# schemprzes.net
KiCad netlist of a schematic drawn in EAGLE
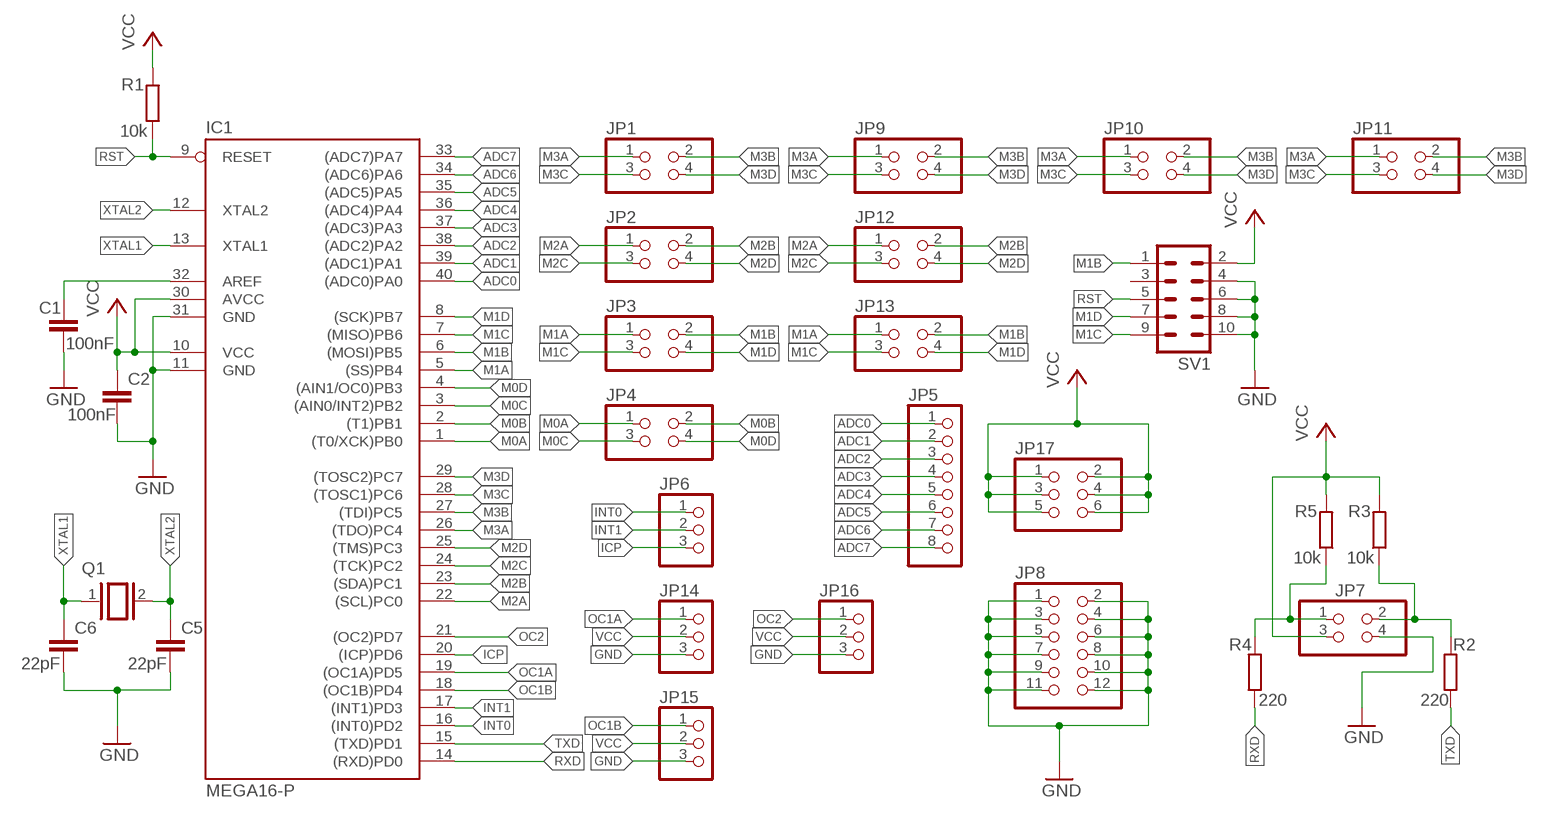
[diagram p0: schematic, sheet 1]

(export (version "E")
  (design (tool "Eeschema 10.0.6"))
  (components
    (comp (ref "C1")
      (value "100nF")
      (footprint "eagle-import:C0805")
      (libsource (lib "eagle-import") (part "C-EUC0805"))
    )
    (comp (ref "C2")
      (value "100nF")
      (footprint "eagle-import:C0805")
      (libsource (lib "eagle-import") (part "C-EUC0805"))
    )
    (comp (ref "C5")
      (value "22pF")
      (footprint "eagle-import:C0805")
      (libsource (lib "eagle-import") (part "C-EUC0805"))
    )
    (comp (ref "C6")
      (value "22pF")
      (footprint "eagle-import:C0805")
      (libsource (lib "eagle-import") (part "C-EUC0805"))
    )
    (comp (ref "IC1")
      (value "MEGA16-P")
      (footprint "eagle-import:DIL40")
      (fields (field (name "MPN") "ATMEGA16-16PU"))
      (libsource (lib "eagle-import") (part "MEGA16-P"))
    )
    (comp (ref "JP1")
      (value "PINHD-2X2")
      (footprint "eagle-import:2X02")
      (libsource (lib "eagle-import") (part "PINHD-2X2"))
    )
    (comp (ref "JP2")
      (value "PINHD-2X2")
      (footprint "eagle-import:2X02")
      (libsource (lib "eagle-import") (part "PINHD-2X2"))
    )
    (comp (ref "JP3")
      (value "PINHD-2X2")
      (footprint "eagle-import:2X02")
      (libsource (lib "eagle-import") (part "PINHD-2X2"))
    )
    (comp (ref "JP4")
      (value "PINHD-2X2")
      (footprint "eagle-import:2X02")
      (libsource (lib "eagle-import") (part "PINHD-2X2"))
    )
    (comp (ref "JP5")
      (value "PINHD-1X8")
      (footprint "eagle-import:1X08")
      (libsource (lib "eagle-import") (part "PINHD-1X8"))
    )
    (comp (ref "JP6")
      (value "PINHD-1X3")
      (footprint "eagle-import:1X03")
      (libsource (lib "eagle-import") (part "PINHD-1X3"))
    )
    (comp (ref "JP7")
      (value "PINHD-2X2")
      (footprint "eagle-import:2X02")
      (libsource (lib "eagle-import") (part "PINHD-2X2"))
    )
    (comp (ref "JP8")
      (value "PINHD-2X6")
      (footprint "eagle-import:2X06")
      (libsource (lib "eagle-import") (part "PINHD-2X6"))
    )
    (comp (ref "JP9")
      (value "PINHD-2X2")
      (footprint "eagle-import:2X02")
      (libsource (lib "eagle-import") (part "PINHD-2X2"))
    )
    (comp (ref "JP10")
      (value "PINHD-2X2")
      (footprint "eagle-import:2X02")
      (libsource (lib "eagle-import") (part "PINHD-2X2"))
    )
    (comp (ref "JP11")
      (value "PINHD-2X2")
      (footprint "eagle-import:2X02")
      (libsource (lib "eagle-import") (part "PINHD-2X2"))
    )
    (comp (ref "JP12")
      (value "PINHD-2X2")
      (footprint "eagle-import:2X02")
      (libsource (lib "eagle-import") (part "PINHD-2X2"))
    )
    (comp (ref "JP13")
      (value "PINHD-2X2")
      (footprint "eagle-import:2X02")
      (libsource (lib "eagle-import") (part "PINHD-2X2"))
    )
    (comp (ref "JP14")
      (value "PINHD-1X3")
      (footprint "eagle-import:1X03")
      (libsource (lib "eagle-import") (part "PINHD-1X3"))
    )
    (comp (ref "JP15")
      (value "PINHD-1X3")
      (footprint "eagle-import:1X03")
      (libsource (lib "eagle-import") (part "PINHD-1X3"))
    )
    (comp (ref "JP16")
      (value "PINHD-1X3")
      (footprint "eagle-import:1X03")
      (libsource (lib "eagle-import") (part "PINHD-1X3"))
    )
    (comp (ref "JP17")
      (value "PINHD-2X3")
      (footprint "eagle-import:2X03")
      (libsource (lib "eagle-import") (part "PINHD-2X3"))
    )
    (comp (ref "Q1")
      (value "XTAL/S")
      (footprint "eagle-import:QS")
      (libsource (lib "eagle-import") (part "XTAL/S"))
    )
    (comp (ref "R1")
      (value "10k")
      (footprint "eagle-import:R0805")
      (libsource (lib "eagle-import") (part "R-EU_R0805"))
    )
    (comp (ref "R2")
      (value "220")
      (footprint "eagle-import:R0805")
      (libsource (lib "eagle-import") (part "R-EU_R0805"))
    )
    (comp (ref "R3")
      (value "10k")
      (footprint "eagle-import:R0805")
      (libsource (lib "eagle-import") (part "R-EU_R0805"))
    )
    (comp (ref "R4")
      (value "220")
      (footprint "eagle-import:R0805")
      (libsource (lib "eagle-import") (part "R-EU_R0805"))
    )
    (comp (ref "R5")
      (value "10k")
      (footprint "eagle-import:R0805")
      (libsource (lib "eagle-import") (part "R-EU_R0805"))
    )
    (comp (ref "SV1")
      (value "ML10")
      (footprint "eagle-import:ML10")
      (libsource (lib "eagle-import") (part "ML10"))
    )
  )
  (nets
    (net (code "1") (name "ADC0") (class "Default")
      (node (ref "IC1") (pin "40") (pinfunction "(ADC0)PA0_40") (pintype "bidirectional"))
      (node (ref "JP5") (pin "1") (pinfunction "1_1") (pintype "passive"))
    )
    (net (code "2") (name "ADC1") (class "Default")
      (node (ref "IC1") (pin "39") (pinfunction "(ADC1)PA1_39") (pintype "bidirectional"))
      (node (ref "JP5") (pin "2") (pinfunction "2_2") (pintype "passive"))
    )
    (net (code "3") (name "ADC2") (class "Default")
      (node (ref "IC1") (pin "38") (pinfunction "(ADC2)PA2_38") (pintype "bidirectional"))
      (node (ref "JP5") (pin "3") (pinfunction "3_3") (pintype "passive"))
    )
    (net (code "4") (name "ADC3") (class "Default")
      (node (ref "IC1") (pin "37") (pinfunction "(ADC3)PA3_37") (pintype "bidirectional"))
      (node (ref "JP5") (pin "4") (pinfunction "4_4") (pintype "passive"))
    )
    (net (code "5") (name "ADC4") (class "Default")
      (node (ref "IC1") (pin "36") (pinfunction "(ADC4)PA4_36") (pintype "bidirectional"))
      (node (ref "JP5") (pin "5") (pinfunction "5_5") (pintype "passive"))
    )
    (net (code "6") (name "ADC5") (class "Default")
      (node (ref "IC1") (pin "35") (pinfunction "(ADC5)PA5_35") (pintype "bidirectional"))
      (node (ref "JP5") (pin "6") (pinfunction "6_6") (pintype "passive"))
    )
    (net (code "7") (name "ADC6") (class "Default")
      (node (ref "IC1") (pin "34") (pinfunction "(ADC6)PA6_34") (pintype "bidirectional"))
      (node (ref "JP5") (pin "7") (pinfunction "7_7") (pintype "passive"))
    )
    (net (code "8") (name "ADC7") (class "Default")
      (node (ref "IC1") (pin "33") (pinfunction "(ADC7)PA7_33") (pintype "bidirectional"))
      (node (ref "JP5") (pin "8") (pinfunction "8_8") (pintype "passive"))
    )
    (net (code "9") (name "GND") (class "Default")
      (node (ref "C1") (pin "2") (pinfunction "2_2") (pintype "passive"))
      (node (ref "C2") (pin "2") (pinfunction "2_2") (pintype "passive"))
      (node (ref "C5") (pin "2") (pinfunction "2_2") (pintype "passive"))
      (node (ref "C6") (pin "2") (pinfunction "2_2") (pintype "passive"))
      (node (ref "IC1") (pin "11") (pinfunction "GND_11") (pintype "power_in"))
      (node (ref "IC1") (pin "31") (pinfunction "GND_31") (pintype "power_in"))
      (node (ref "JP14") (pin "3") (pinfunction "3_3") (pintype "passive"))
      (node (ref "JP15") (pin "3") (pinfunction "3_3") (pintype "passive"))
      (node (ref "JP16") (pin "3") (pinfunction "3_3") (pintype "passive"))
      (node (ref "JP7") (pin "4") (pinfunction "4_4") (pintype "passive"))
      (node (ref "JP8") (pin "1") (pinfunction "1_1") (pintype "passive"))
      (node (ref "JP8") (pin "10") (pinfunction "10_10") (pintype "passive"))
      (node (ref "JP8") (pin "11") (pinfunction "11_11") (pintype "passive"))
      (node (ref "JP8") (pin "12") (pinfunction "12_12") (pintype "passive"))
      (node (ref "JP8") (pin "2") (pinfunction "2_2") (pintype "passive"))
      (node (ref "JP8") (pin "3") (pinfunction "3_3") (pintype "passive"))
      (node (ref "JP8") (pin "4") (pinfunction "4_4") (pintype "passive"))
      (node (ref "JP8") (pin "5") (pinfunction "5_5") (pintype "passive"))
      (node (ref "JP8") (pin "6") (pinfunction "6_6") (pintype "passive"))
      (node (ref "JP8") (pin "7") (pinfunction "7_7") (pintype "passive"))
      (node (ref "JP8") (pin "8") (pinfunction "8_8") (pintype "passive"))
      (node (ref "JP8") (pin "9") (pinfunction "9_9") (pintype "passive"))
      (node (ref "SV1") (pin "10") (pinfunction "10_10") (pintype "passive"))
      (node (ref "SV1") (pin "4") (pinfunction "4_4") (pintype "passive"))
      (node (ref "SV1") (pin "6") (pinfunction "6_6") (pintype "passive"))
      (node (ref "SV1") (pin "8") (pinfunction "8_8") (pintype "passive"))
    )
    (net (code "10") (name "ICP") (class "Default")
      (node (ref "IC1") (pin "20") (pinfunction "(ICP)PD6_20") (pintype "bidirectional"))
      (node (ref "JP6") (pin "3") (pinfunction "3_3") (pintype "passive"))
    )
    (net (code "11") (name "INT0") (class "Default")
      (node (ref "IC1") (pin "16") (pinfunction "(INT0)PD2_16") (pintype "bidirectional"))
      (node (ref "JP6") (pin "1") (pinfunction "1_1") (pintype "passive"))
    )
    (net (code "12") (name "INT1") (class "Default")
      (node (ref "IC1") (pin "17") (pinfunction "(INT1)PD3_17") (pintype "bidirectional"))
      (node (ref "JP6") (pin "2") (pinfunction "2_2") (pintype "passive"))
    )
    (net (code "13") (name "M0A") (class "Default")
      (node (ref "IC1") (pin "1") (pinfunction "(T0/XCK)PB0_1") (pintype "bidirectional"))
      (node (ref "JP4") (pin "1") (pinfunction "1_1") (pintype "passive"))
    )
    (net (code "14") (name "M0B") (class "Default")
      (node (ref "IC1") (pin "2") (pinfunction "(T1)PB1_2") (pintype "bidirectional"))
      (node (ref "JP4") (pin "2") (pinfunction "2_2") (pintype "passive"))
    )
    (net (code "15") (name "M0C") (class "Default")
      (node (ref "IC1") (pin "3") (pinfunction "(AIN0/INT2)PB2_3") (pintype "bidirectional"))
      (node (ref "JP4") (pin "3") (pinfunction "3_3") (pintype "passive"))
    )
    (net (code "16") (name "M0D") (class "Default")
      (node (ref "IC1") (pin "4") (pinfunction "(AIN1/OC0)PB3_4") (pintype "bidirectional"))
      (node (ref "JP4") (pin "4") (pinfunction "4_4") (pintype "passive"))
    )
    (net (code "17") (name "M1A") (class "Default")
      (node (ref "IC1") (pin "5") (pinfunction "(SS)PB4_5") (pintype "bidirectional"))
      (node (ref "JP13") (pin "1") (pinfunction "1_1") (pintype "passive"))
      (node (ref "JP3") (pin "1") (pinfunction "1_1") (pintype "passive"))
    )
    (net (code "18") (name "M1B") (class "Default")
      (node (ref "IC1") (pin "6") (pinfunction "(MOSI)PB5_6") (pintype "bidirectional"))
      (node (ref "JP13") (pin "2") (pinfunction "2_2") (pintype "passive"))
      (node (ref "JP3") (pin "2") (pinfunction "2_2") (pintype "passive"))
      (node (ref "SV1") (pin "1") (pinfunction "1_1") (pintype "passive"))
    )
    (net (code "19") (name "M1C") (class "Default")
      (node (ref "IC1") (pin "7") (pinfunction "(MISO)PB6_7") (pintype "bidirectional"))
      (node (ref "JP13") (pin "3") (pinfunction "3_3") (pintype "passive"))
      (node (ref "JP3") (pin "3") (pinfunction "3_3") (pintype "passive"))
      (node (ref "SV1") (pin "9") (pinfunction "9_9") (pintype "passive"))
    )
    (net (code "20") (name "M1D") (class "Default")
      (node (ref "IC1") (pin "8") (pinfunction "(SCK)PB7_8") (pintype "bidirectional"))
      (node (ref "JP13") (pin "4") (pinfunction "4_4") (pintype "passive"))
      (node (ref "JP3") (pin "4") (pinfunction "4_4") (pintype "passive"))
      (node (ref "SV1") (pin "7") (pinfunction "7_7") (pintype "passive"))
    )
    (net (code "21") (name "M2A") (class "Default")
      (node (ref "IC1") (pin "22") (pinfunction "(SCL)PC0_22") (pintype "bidirectional"))
      (node (ref "JP12") (pin "1") (pinfunction "1_1") (pintype "passive"))
      (node (ref "JP2") (pin "1") (pinfunction "1_1") (pintype "passive"))
    )
    (net (code "22") (name "M2B") (class "Default")
      (node (ref "IC1") (pin "23") (pinfunction "(SDA)PC1_23") (pintype "bidirectional"))
      (node (ref "JP12") (pin "2") (pinfunction "2_2") (pintype "passive"))
      (node (ref "JP2") (pin "2") (pinfunction "2_2") (pintype "passive"))
    )
    (net (code "23") (name "M2C") (class "Default")
      (node (ref "IC1") (pin "24") (pinfunction "(TCK)PC2_24") (pintype "bidirectional"))
      (node (ref "JP12") (pin "3") (pinfunction "3_3") (pintype "passive"))
      (node (ref "JP2") (pin "3") (pinfunction "3_3") (pintype "passive"))
    )
    (net (code "24") (name "M2D") (class "Default")
      (node (ref "IC1") (pin "25") (pinfunction "(TMS)PC3_25") (pintype "bidirectional"))
      (node (ref "JP12") (pin "4") (pinfunction "4_4") (pintype "passive"))
      (node (ref "JP2") (pin "4") (pinfunction "4_4") (pintype "passive"))
    )
    (net (code "25") (name "M3A") (class "Default")
      (node (ref "IC1") (pin "26") (pinfunction "(TDO)PC4_26") (pintype "bidirectional"))
      (node (ref "JP1") (pin "1") (pinfunction "1_1") (pintype "passive"))
      (node (ref "JP10") (pin "1") (pinfunction "1_1") (pintype "passive"))
      (node (ref "JP11") (pin "1") (pinfunction "1_1") (pintype "passive"))
      (node (ref "JP9") (pin "1") (pinfunction "1_1") (pintype "passive"))
    )
    (net (code "26") (name "M3B") (class "Default")
      (node (ref "IC1") (pin "27") (pinfunction "(TDI)PC5_27") (pintype "bidirectional"))
      (node (ref "JP1") (pin "2") (pinfunction "2_2") (pintype "passive"))
      (node (ref "JP10") (pin "2") (pinfunction "2_2") (pintype "passive"))
      (node (ref "JP11") (pin "2") (pinfunction "2_2") (pintype "passive"))
      (node (ref "JP9") (pin "2") (pinfunction "2_2") (pintype "passive"))
    )
    (net (code "27") (name "M3C") (class "Default")
      (node (ref "IC1") (pin "28") (pinfunction "(TOSC1)PC6_28") (pintype "bidirectional"))
      (node (ref "JP1") (pin "3") (pinfunction "3_3") (pintype "passive"))
      (node (ref "JP10") (pin "3") (pinfunction "3_3") (pintype "passive"))
      (node (ref "JP11") (pin "3") (pinfunction "3_3") (pintype "passive"))
      (node (ref "JP9") (pin "3") (pinfunction "3_3") (pintype "passive"))
    )
    (net (code "28") (name "M3D") (class "Default")
      (node (ref "IC1") (pin "29") (pinfunction "(TOSC2)PC7_29") (pintype "bidirectional"))
      (node (ref "JP1") (pin "4") (pinfunction "4_4") (pintype "passive"))
      (node (ref "JP10") (pin "4") (pinfunction "4_4") (pintype "passive"))
      (node (ref "JP11") (pin "4") (pinfunction "4_4") (pintype "passive"))
      (node (ref "JP9") (pin "4") (pinfunction "4_4") (pintype "passive"))
    )
    (net (code "29") (name "Net-(IC1-AREF)") (class "Default")
      (node (ref "C1") (pin "1") (pinfunction "1_1") (pintype "passive"))
      (node (ref "IC1") (pin "32") (pinfunction "AREF_32") (pintype "passive"))
    )
    (net (code "30") (name "Net-(JP7-Pad1)") (class "Default")
      (node (ref "JP7") (pin "1") (pinfunction "1_1") (pintype "passive"))
      (node (ref "R4") (pin "2") (pinfunction "2_2") (pintype "passive"))
      (node (ref "R5") (pin "1") (pinfunction "1_1") (pintype "passive"))
    )
    (net (code "31") (name "Net-(JP7-Pad2)") (class "Default")
      (node (ref "JP7") (pin "2") (pinfunction "2_2") (pintype "passive"))
      (node (ref "R2") (pin "2") (pinfunction "2_2") (pintype "passive"))
      (node (ref "R3") (pin "1") (pinfunction "1_1") (pintype "passive"))
    )
    (net (code "32") (name "OC1A") (class "Default")
      (node (ref "IC1") (pin "19") (pinfunction "(OC1A)PD5_19") (pintype "bidirectional"))
      (node (ref "JP14") (pin "1") (pinfunction "1_1") (pintype "passive"))
    )
    (net (code "33") (name "OC1B") (class "Default")
      (node (ref "IC1") (pin "18") (pinfunction "(OC1B)PD4_18") (pintype "bidirectional"))
      (node (ref "JP15") (pin "1") (pinfunction "1_1") (pintype "passive"))
    )
    (net (code "34") (name "OC2") (class "Default")
      (node (ref "IC1") (pin "21") (pinfunction "(OC2)PD7_21") (pintype "bidirectional"))
      (node (ref "JP16") (pin "1") (pinfunction "1_1") (pintype "passive"))
    )
    (net (code "35") (name "RST") (class "Default")
      (node (ref "IC1") (pin "9") (pinfunction "RESET_9") (pintype "input"))
      (node (ref "R1") (pin "1") (pinfunction "1_1") (pintype "passive"))
      (node (ref "SV1") (pin "5") (pinfunction "5_5") (pintype "passive"))
    )
    (net (code "36") (name "RXD") (class "Default")
      (node (ref "IC1") (pin "14") (pinfunction "(RXD)PD0_14") (pintype "bidirectional"))
      (node (ref "R4") (pin "1") (pinfunction "1_1") (pintype "passive"))
    )
    (net (code "37") (name "TXD") (class "Default")
      (node (ref "IC1") (pin "15") (pinfunction "(TXD)PD1_15") (pintype "bidirectional"))
      (node (ref "R2") (pin "1") (pinfunction "1_1") (pintype "passive"))
    )
    (net (code "38") (name "VCC") (class "Default")
      (node (ref "C2") (pin "1") (pinfunction "1_1") (pintype "passive"))
      (node (ref "IC1") (pin "10") (pinfunction "VCC_10") (pintype "power_in"))
      (node (ref "IC1") (pin "30") (pinfunction "AVCC_30") (pintype "power_in"))
      (node (ref "JP14") (pin "2") (pinfunction "2_2") (pintype "passive"))
      (node (ref "JP15") (pin "2") (pinfunction "2_2") (pintype "passive"))
      (node (ref "JP16") (pin "2") (pinfunction "2_2") (pintype "passive"))
      (node (ref "JP17") (pin "1") (pinfunction "1_1") (pintype "passive"))
      (node (ref "JP17") (pin "2") (pinfunction "2_2") (pintype "passive"))
      (node (ref "JP17") (pin "3") (pinfunction "3_3") (pintype "passive"))
      (node (ref "JP17") (pin "4") (pinfunction "4_4") (pintype "passive"))
      (node (ref "JP17") (pin "5") (pinfunction "5_5") (pintype "passive"))
      (node (ref "JP17") (pin "6") (pinfunction "6_6") (pintype "passive"))
      (node (ref "JP7") (pin "3") (pinfunction "3_3") (pintype "passive"))
      (node (ref "R1") (pin "2") (pinfunction "2_2") (pintype "passive"))
      (node (ref "R3") (pin "2") (pinfunction "2_2") (pintype "passive"))
      (node (ref "R5") (pin "2") (pinfunction "2_2") (pintype "passive"))
      (node (ref "SV1") (pin "2") (pinfunction "2_2") (pintype "passive"))
    )
    (net (code "39") (name "XTAL1") (class "Default")
      (node (ref "C6") (pin "1") (pinfunction "1_1") (pintype "passive"))
      (node (ref "IC1") (pin "13") (pinfunction "XTAL1_13") (pintype "bidirectional"))
      (node (ref "Q1") (pin "1") (pinfunction "1_1") (pintype "passive"))
    )
    (net (code "40") (name "XTAL2") (class "Default")
      (node (ref "C5") (pin "1") (pinfunction "1_1") (pintype "passive"))
      (node (ref "IC1") (pin "12") (pinfunction "XTAL2_12") (pintype "bidirectional"))
      (node (ref "Q1") (pin "2") (pinfunction "2_2") (pintype "passive"))
    )
    (net (code "41") (name "unconnected-(SV1-Pad3)") (class "Default")
      (node (ref "SV1") (pin "3") (pinfunction "3_3") (pintype "passive"))
    )
  )
)
